# Sensors.net
KiCad netlist of a schematic drawn in Altium Designer
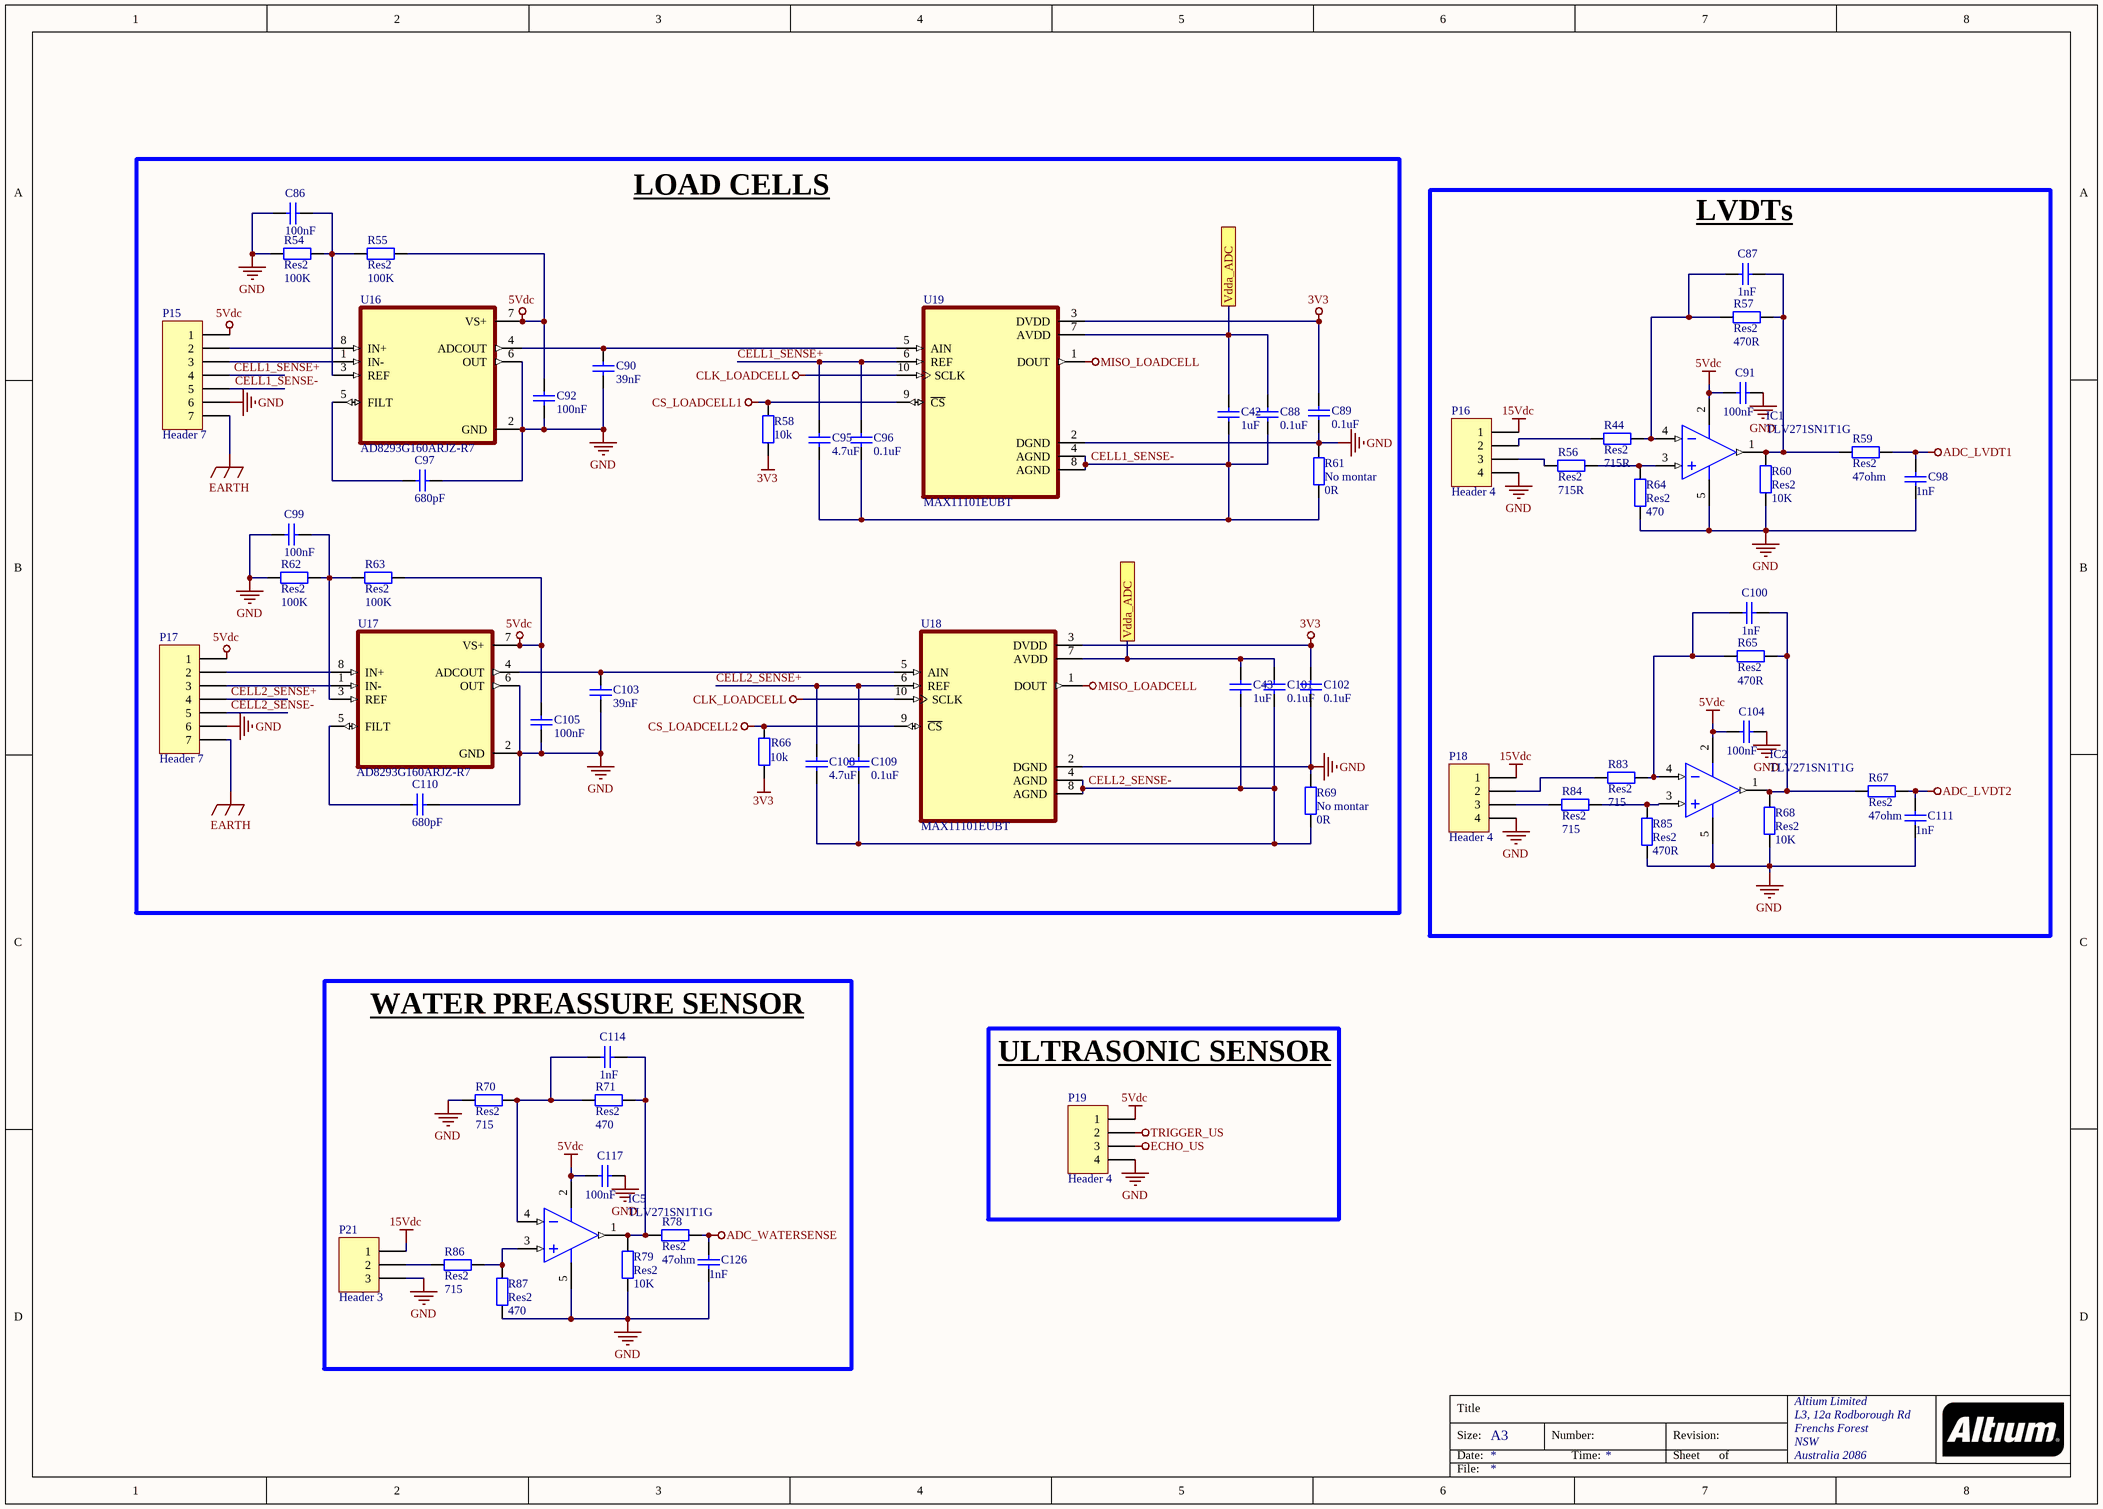
[diagram p0: Sensors.SchDoc]

(export (version "E")
  (design (tool "Eeschema 10.0.6"))
  (components
    (comp (ref "C42")
      (value "1uF")
      (footprint "Miscellaneous Devices:0603 - duplicate")
      (description "Capacitor")
      (fields (field (name "Comment") "Cap") (field (name "PUBLISHER") "Altium Limited"))
      (libsource (lib "Miscellaneous Devices") (part "Cap"))
    )
    (comp (ref "C43")
      (value "1uF")
      (footprint "Miscellaneous Devices:0603 - duplicate")
      (description "Capacitor")
      (fields (field (name "Comment") "Cap") (field (name "PUBLISHER") "Altium Limited"))
      (libsource (lib "Miscellaneous Devices") (part "Cap"))
    )
    (comp (ref "C86")
      (value "100nF")
      (footprint "Miscellaneous Devices:0603 - duplicate")
      (description "Capacitor")
      (fields (field (name "Comment") "Cap") (field (name "PUBLISHER") "Altium Limited"))
      (libsource (lib "Miscellaneous Devices") (part "Cap"))
    )
    (comp (ref "C87")
      (value "1nF")
      (footprint "Miscellaneous Devices:0603 - duplicate")
      (description "Capacitor")
      (fields (field (name "Comment") "Cap") (field (name "PUBLISHER") "Altium Limited"))
      (libsource (lib "Miscellaneous Devices") (part "Cap"))
    )
    (comp (ref "C88")
      (value "0.1uF")
      (footprint "Miscellaneous Devices:0603 - duplicate")
      (description "Capacitor")
      (fields (field (name "Comment") "Cap") (field (name "PUBLISHER") "Altium Limited"))
      (libsource (lib "Miscellaneous Devices") (part "Cap"))
    )
    (comp (ref "C89")
      (value "0.1uF")
      (footprint "Miscellaneous Devices:0603 - duplicate")
      (description "Capacitor")
      (fields (field (name "Comment") "Cap") (field (name "PUBLISHER") "Altium Limited"))
      (libsource (lib "Miscellaneous Devices") (part "Cap"))
    )
    (comp (ref "C90")
      (value "39nF")
      (footprint "Miscellaneous Devices:0603 - duplicate")
      (description "Capacitor")
      (fields (field (name "Comment") "Cap") (field (name "PUBLISHER") "Altium Limited"))
      (libsource (lib "Miscellaneous Devices") (part "Cap"))
    )
    (comp (ref "C91")
      (value "100nF")
      (footprint "Miscellaneous Devices:0603 - duplicate")
      (description "Capacitor")
      (fields (field (name "Comment") "Cap") (field (name "PUBLISHER") "Altium Limited"))
      (libsource (lib "Miscellaneous Devices") (part "Cap"))
    )
    (comp (ref "C92")
      (value "100nF")
      (footprint "Miscellaneous Devices:0603 - duplicate")
      (description "Capacitor")
      (fields (field (name "Comment") "Cap") (field (name "PUBLISHER") "Altium Limited"))
      (libsource (lib "Miscellaneous Devices") (part "Cap"))
    )
    (comp (ref "C95")
      (value "4.7uF")
      (footprint "Miscellaneous Devices:0603 - duplicate")
      (description "Capacitor")
      (fields (field (name "Comment") "Cap") (field (name "PUBLISHER") "Altium Limited"))
      (libsource (lib "Miscellaneous Devices") (part "Cap"))
    )
    (comp (ref "C96")
      (value "0.1uF")
      (footprint "Miscellaneous Devices:0603 - duplicate")
      (description "Capacitor")
      (fields (field (name "Comment") "Cap") (field (name "PUBLISHER") "Altium Limited"))
      (libsource (lib "Miscellaneous Devices") (part "Cap"))
    )
    (comp (ref "C97")
      (value "680pF")
      (footprint "Miscellaneous Devices:0603 - duplicate")
      (description "Capacitor")
      (fields (field (name "Comment") "Cap") (field (name "PUBLISHER") "Altium Limited"))
      (libsource (lib "Miscellaneous Devices") (part "Cap"))
    )
    (comp (ref "C98")
      (value "1nF")
      (footprint "Miscellaneous Devices:0603 - duplicate")
      (description "Capacitor")
      (fields (field (name "Comment") "Cap") (field (name "PUBLISHER") "Altium Limited"))
      (libsource (lib "Miscellaneous Devices") (part "Cap"))
    )
    (comp (ref "C99")
      (value "100nF")
      (footprint "Miscellaneous Devices:0603 - duplicate")
      (description "Capacitor")
      (fields (field (name "Comment") "Cap") (field (name "PUBLISHER") "Altium Limited"))
      (libsource (lib "Miscellaneous Devices") (part "Cap"))
    )
    (comp (ref "C100")
      (value "1nF")
      (footprint "Miscellaneous Devices:0603 - duplicate")
      (description "Capacitor")
      (fields (field (name "Comment") "Cap") (field (name "PUBLISHER") "Altium Limited"))
      (libsource (lib "Miscellaneous Devices") (part "Cap"))
    )
    (comp (ref "C101")
      (value "0.1uF")
      (footprint "Miscellaneous Devices:0603 - duplicate")
      (description "Capacitor")
      (fields (field (name "Comment") "Cap") (field (name "PUBLISHER") "Altium Limited"))
      (libsource (lib "Miscellaneous Devices") (part "Cap"))
    )
    (comp (ref "C102")
      (value "0.1uF")
      (footprint "Miscellaneous Devices:0603 - duplicate")
      (description "Capacitor")
      (fields (field (name "Comment") "Cap") (field (name "PUBLISHER") "Altium Limited"))
      (libsource (lib "Miscellaneous Devices") (part "Cap"))
    )
    (comp (ref "C103")
      (value "39nF")
      (footprint "Miscellaneous Devices:0603 - duplicate")
      (description "Capacitor")
      (fields (field (name "Comment") "Cap") (field (name "PUBLISHER") "Altium Limited"))
      (libsource (lib "Miscellaneous Devices") (part "Cap"))
    )
    (comp (ref "C104")
      (value "100nF")
      (footprint "Miscellaneous Devices:0603 - duplicate")
      (description "Capacitor")
      (fields (field (name "Comment") "Cap") (field (name "PUBLISHER") "Altium Limited"))
      (libsource (lib "Miscellaneous Devices") (part "Cap"))
    )
    (comp (ref "C105")
      (value "100nF")
      (footprint "Miscellaneous Devices:0603 - duplicate")
      (description "Capacitor")
      (fields (field (name "Comment") "Cap") (field (name "PUBLISHER") "Altium Limited"))
      (libsource (lib "Miscellaneous Devices") (part "Cap"))
    )
    (comp (ref "C108")
      (value "4.7uF")
      (footprint "Miscellaneous Devices:0603 - duplicate")
      (description "Capacitor")
      (fields (field (name "Comment") "Cap") (field (name "PUBLISHER") "Altium Limited"))
      (libsource (lib "Miscellaneous Devices") (part "Cap"))
    )
    (comp (ref "C109")
      (value "0.1uF")
      (footprint "Miscellaneous Devices:0603 - duplicate")
      (description "Capacitor")
      (fields (field (name "Comment") "Cap") (field (name "PUBLISHER") "Altium Limited"))
      (libsource (lib "Miscellaneous Devices") (part "Cap"))
    )
    (comp (ref "C110")
      (value "680pF")
      (footprint "Miscellaneous Devices:0603 - duplicate")
      (description "Capacitor")
      (fields (field (name "Comment") "Cap") (field (name "PUBLISHER") "Altium Limited"))
      (libsource (lib "Miscellaneous Devices") (part "Cap"))
    )
    (comp (ref "C111")
      (value "1nF")
      (footprint "Miscellaneous Devices:0603 - duplicate")
      (description "Capacitor")
      (fields (field (name "Comment") "Cap") (field (name "PUBLISHER") "Altium Limited"))
      (libsource (lib "Miscellaneous Devices") (part "Cap"))
    )
    (comp (ref "C114")
      (value "1nF")
      (footprint "Miscellaneous Devices:0603 - duplicate")
      (description "Capacitor")
      (fields (field (name "Comment") "Cap") (field (name "PUBLISHER") "Altium Limited"))
      (libsource (lib "Miscellaneous Devices") (part "Cap"))
    )
    (comp (ref "C117")
      (value "100nF")
      (footprint "Miscellaneous Devices:0603 - duplicate")
      (description "Capacitor")
      (fields (field (name "Comment") "Cap") (field (name "PUBLISHER") "Altium Limited"))
      (libsource (lib "Miscellaneous Devices") (part "Cap"))
    )
    (comp (ref "C126")
      (value "1nF")
      (footprint "Miscellaneous Devices:0603 - duplicate")
      (description "Capacitor")
      (fields (field (name "Comment") "Cap") (field (name "PUBLISHER") "Altium Limited"))
      (libsource (lib "Miscellaneous Devices") (part "Cap"))
    )
    (comp (ref "IC1")
      (value "TLV271SN1T1G")
      (footprint "Miscellaneous Devices:SOT23-5_N")
      (description "Operational Amplifier")
      (fields (field (name "PUBLISHER") "Altium Limited"))
      (libsource (lib "Miscellaneous Devices") (part "TLV271SN1T1G"))
    )
    (comp (ref "IC2")
      (value "TLV271SN1T1G")
      (footprint "Miscellaneous Devices:SOT23-5_N")
      (description "Operational Amplifier")
      (fields (field (name "PUBLISHER") "Altium Limited"))
      (libsource (lib "Miscellaneous Devices") (part "TLV271SN1T1G"))
    )
    (comp (ref "IC5")
      (value "TLV271SN1T1G")
      (footprint "Miscellaneous Devices:SOT23-5_N")
      (description "Operational Amplifier")
      (fields (field (name "PUBLISHER") "Altium Limited"))
      (libsource (lib "Miscellaneous Devices") (part "TLV271SN1T1G"))
    )
    (comp (ref "P15")
      (value "Header 7")
      (footprint "Miscellaneous Connectors:regleta_7")
      (description "Header, 7-Pin")
      (fields (field (name "PUBLISHER") "Altium Limited"))
      (libsource (lib "Miscellaneous Connectors") (part "Header 7"))
    )
    (comp (ref "P16")
      (value "Header 4")
      (footprint "Miscellaneous Connectors:regleta_4")
      (description "Header, 4-Pin")
      (fields (field (name "PUBLISHER") "Altium Limited"))
      (libsource (lib "Miscellaneous Connectors") (part "Header 4"))
    )
    (comp (ref "P17")
      (value "Header 7")
      (footprint "Miscellaneous Connectors:regleta_7")
      (description "Header, 7-Pin")
      (fields (field (name "PUBLISHER") "Altium Limited"))
      (libsource (lib "Miscellaneous Connectors") (part "Header 7"))
    )
    (comp (ref "P18")
      (value "Header 4")
      (footprint "Miscellaneous Connectors:regleta_4")
      (description "Header, 4-Pin")
      (fields (field (name "PUBLISHER") "Altium Limited"))
      (libsource (lib "Miscellaneous Connectors") (part "Header 4"))
    )
    (comp (ref "P19")
      (value "Header 4")
      (footprint "Miscellaneous Connectors:regleta_4")
      (description "Header, 4-Pin")
      (fields (field (name "PUBLISHER") "Altium Limited"))
      (libsource (lib "Miscellaneous Connectors") (part "Header 4"))
    )
    (comp (ref "P21")
      (value "Header 3")
      (footprint "Miscellaneous Connectors:regleta_3")
      (description "Header, 3-Pin")
      (fields (field (name "PUBLISHER") "Altium Limited"))
      (libsource (lib "Miscellaneous Connectors") (part "Header 3"))
    )
    (comp (ref "R44")
      (value "Res2")
      (footprint "Miscellaneous Devices:0603 - duplicate")
      (description "Resistor")
      (fields (field (name "ALTIUM_VALUE") "715R") (field (name "PUBLISHER") "Altium Limited"))
      (libsource (lib "Miscellaneous Devices") (part "Res2"))
    )
    (comp (ref "R54")
      (value "Res2")
      (footprint "Miscellaneous Devices:0603 - duplicate")
      (description "Resistor")
      (fields (field (name "ALTIUM_VALUE") "100K") (field (name "PUBLISHER") "Altium Limited"))
      (libsource (lib "Miscellaneous Devices") (part "Res2"))
    )
    (comp (ref "R55")
      (value "Res2")
      (footprint "Miscellaneous Devices:0603 - duplicate")
      (description "Resistor")
      (fields (field (name "ALTIUM_VALUE") "100K") (field (name "PUBLISHER") "Altium Limited"))
      (libsource (lib "Miscellaneous Devices") (part "Res2"))
    )
    (comp (ref "R56")
      (value "Res2")
      (footprint "Miscellaneous Devices:0603 - duplicate")
      (description "Resistor")
      (fields (field (name "ALTIUM_VALUE") "715R") (field (name "PUBLISHER") "Altium Limited"))
      (libsource (lib "Miscellaneous Devices") (part "Res2"))
    )
    (comp (ref "R57")
      (value "Res2")
      (footprint "Miscellaneous Devices:0603 - duplicate")
      (description "Resistor")
      (fields (field (name "ALTIUM_VALUE") "470R") (field (name "PUBLISHER") "Altium Limited"))
      (libsource (lib "Miscellaneous Devices") (part "Res2"))
    )
    (comp (ref "R58")
      (value "10k")
      (footprint "Miscellaneous Devices:0603 - duplicate")
      (description "Resistor")
      (fields (field (name "PUBLISHER") "Altium Limited"))
      (libsource (lib "") (part "Res2_2"))
    )
    (comp (ref "R59")
      (value "Res2")
      (footprint "Miscellaneous Devices:0603 - duplicate")
      (description "Resistor")
      (fields (field (name "ALTIUM_VALUE") "47ohm") (field (name "PUBLISHER") "Altium Limited"))
      (libsource (lib "Miscellaneous Devices") (part "Res2"))
    )
    (comp (ref "R60")
      (value "Res2")
      (footprint "Miscellaneous Devices:0603 - duplicate")
      (description "Resistor")
      (fields (field (name "ALTIUM_VALUE") "10K") (field (name "PUBLISHER") "Altium Limited"))
      (libsource (lib "") (part "Res2_1"))
    )
    (comp (ref "R61")
      (value "No montar")
      (footprint "Miscellaneous Devices:0603 - duplicate")
      (description "Resistor")
      (fields (field (name "ALTIUM_VALUE") "0R") (field (name "PUBLISHER") "Altium Limited"))
      (libsource (lib "") (part "Res2_1"))
    )
    (comp (ref "R62")
      (value "Res2")
      (footprint "Miscellaneous Devices:0603 - duplicate")
      (description "Resistor")
      (fields (field (name "ALTIUM_VALUE") "100K") (field (name "PUBLISHER") "Altium Limited"))
      (libsource (lib "Miscellaneous Devices") (part "Res2"))
    )
    (comp (ref "R63")
      (value "Res2")
      (footprint "Miscellaneous Devices:0603 - duplicate")
      (description "Resistor")
      (fields (field (name "ALTIUM_VALUE") "100K") (field (name "PUBLISHER") "Altium Limited"))
      (libsource (lib "Miscellaneous Devices") (part "Res2"))
    )
    (comp (ref "R64")
      (value "Res2")
      (footprint "Miscellaneous Devices:0603 - duplicate")
      (description "Resistor")
      (fields (field (name "ALTIUM_VALUE") "470") (field (name "PUBLISHER") "Altium Limited"))
      (libsource (lib "") (part "Res2_2"))
    )
    (comp (ref "R65")
      (value "Res2")
      (footprint "Miscellaneous Devices:0603 - duplicate")
      (description "Resistor")
      (fields (field (name "ALTIUM_VALUE") "470R") (field (name "PUBLISHER") "Altium Limited"))
      (libsource (lib "Miscellaneous Devices") (part "Res2"))
    )
    (comp (ref "R66")
      (value "10k")
      (footprint "Miscellaneous Devices:0603 - duplicate")
      (description "Resistor")
      (fields (field (name "PUBLISHER") "Altium Limited"))
      (libsource (lib "") (part "Res2_2"))
    )
    (comp (ref "R67")
      (value "Res2")
      (footprint "Miscellaneous Devices:0603 - duplicate")
      (description "Resistor")
      (fields (field (name "ALTIUM_VALUE") "47ohm") (field (name "PUBLISHER") "Altium Limited"))
      (libsource (lib "Miscellaneous Devices") (part "Res2"))
    )
    (comp (ref "R68")
      (value "Res2")
      (footprint "Miscellaneous Devices:0603 - duplicate")
      (description "Resistor")
      (fields (field (name "ALTIUM_VALUE") "10K") (field (name "PUBLISHER") "Altium Limited"))
      (libsource (lib "") (part "Res2_1"))
    )
    (comp (ref "R69")
      (value "No montar")
      (footprint "Miscellaneous Devices:0603 - duplicate")
      (description "Resistor")
      (fields (field (name "ALTIUM_VALUE") "0R") (field (name "PUBLISHER") "Altium Limited"))
      (libsource (lib "") (part "Res2_1"))
    )
    (comp (ref "R70")
      (value "Res2")
      (footprint "Miscellaneous Devices:0603 - duplicate")
      (description "Resistor")
      (fields (field (name "ALTIUM_VALUE") "715") (field (name "PUBLISHER") "Altium Limited"))
      (libsource (lib "Miscellaneous Devices") (part "Res2"))
    )
    (comp (ref "R71")
      (value "Res2")
      (footprint "Miscellaneous Devices:0603 - duplicate")
      (description "Resistor")
      (fields (field (name "ALTIUM_VALUE") "470") (field (name "PUBLISHER") "Altium Limited"))
      (libsource (lib "Miscellaneous Devices") (part "Res2"))
    )
    (comp (ref "R78")
      (value "Res2")
      (footprint "Miscellaneous Devices:0603 - duplicate")
      (description "Resistor")
      (fields (field (name "ALTIUM_VALUE") "47ohm") (field (name "PUBLISHER") "Altium Limited"))
      (libsource (lib "Miscellaneous Devices") (part "Res2"))
    )
    (comp (ref "R79")
      (value "Res2")
      (footprint "Miscellaneous Devices:0603 - duplicate")
      (description "Resistor")
      (fields (field (name "ALTIUM_VALUE") "10K") (field (name "PUBLISHER") "Altium Limited"))
      (libsource (lib "") (part "Res2_1"))
    )
    (comp (ref "R83")
      (value "Res2")
      (footprint "Miscellaneous Devices:0603 - duplicate")
      (description "Resistor")
      (fields (field (name "ALTIUM_VALUE") "715") (field (name "PUBLISHER") "Altium Limited"))
      (libsource (lib "Miscellaneous Devices") (part "Res2"))
    )
    (comp (ref "R84")
      (value "Res2")
      (footprint "Miscellaneous Devices:0603 - duplicate")
      (description "Resistor")
      (fields (field (name "ALTIUM_VALUE") "715") (field (name "PUBLISHER") "Altium Limited"))
      (libsource (lib "Miscellaneous Devices") (part "Res2"))
    )
    (comp (ref "R85")
      (value "Res2")
      (footprint "Miscellaneous Devices:0603 - duplicate")
      (description "Resistor")
      (fields (field (name "ALTIUM_VALUE") "470R") (field (name "PUBLISHER") "Altium Limited"))
      (libsource (lib "") (part "Res2_2"))
    )
    (comp (ref "R86")
      (value "Res2")
      (footprint "Miscellaneous Devices:0603 - duplicate")
      (description "Resistor")
      (fields (field (name "ALTIUM_VALUE") "715") (field (name "PUBLISHER") "Altium Limited"))
      (libsource (lib "Miscellaneous Devices") (part "Res2"))
    )
    (comp (ref "R87")
      (value "Res2")
      (footprint "Miscellaneous Devices:0603 - duplicate")
      (description "Resistor")
      (fields (field (name "ALTIUM_VALUE") "470") (field (name "PUBLISHER") "Altium Limited"))
      (libsource (lib "") (part "Res2_2"))
    )
    (comp (ref "U16")
      (value "AD8293G160ARJZ-R7")
      (footprint "Miscellaneous Devices:SOT65P280X145-8N")
      (description "Instrumentation Amplifier 1 Circuit Rail-to-Rail SOT-23-8")
      (fields (field (name "MF") "Analog Devices"))
      (libsource (lib "Miscellaneous Devices") (part "AD8293G160ARJZ-R7"))
    )
    (comp (ref "U17")
      (value "AD8293G160ARJZ-R7")
      (footprint "Miscellaneous Devices:SOT65P280X145-8N")
      (description "Instrumentation Amplifier 1 Circuit Rail-to-Rail SOT-23-8")
      (fields (field (name "MF") "Analog Devices"))
      (libsource (lib "Miscellaneous Devices") (part "AD8293G160ARJZ-R7"))
    )
    (comp (ref "U18")
      (value "MAX11101EUBT")
      (footprint "Miscellaneous Devices:SOP50P490X110-10N")
      (description "Data acquisition IC - AD converter _ADC_ Maxim Integrated MAX11101EUB+T External uMAX 10")
      (fields (field (name "MP") "MAX11101EUB+T") (field (name "MF") "Maxim Integrated"))
      (libsource (lib "Miscellaneous Devices") (part "MAX11101EUBT"))
    )
    (comp (ref "U19")
      (value "MAX11101EUBT")
      (footprint "Miscellaneous Devices:SOP50P490X110-10N")
      (description "Data acquisition IC - AD converter _ADC_ Maxim Integrated MAX11101EUB+T External uMAX 10")
      (fields (field (name "MP") "MAX11101EUB+T") (field (name "MF") "Maxim Integrated"))
      (libsource (lib "Miscellaneous Devices") (part "MAX11101EUBT"))
    )
  )
  (nets
    (net (code "1") (name "/CELL1_SENSE+") (class "Default")
      (node (ref "C95") (pin "2") (pinfunction "2_2") (pintype "passive"))
      (node (ref "C96") (pin "2") (pinfunction "2_2") (pintype "passive"))
      (node (ref "P15") (pin "4") (pinfunction "4_4") (pintype "passive"))
      (node (ref "U19") (pin "6") (pinfunction "REF_6") (pintype "input"))
    )
    (net (code "2") (name "/CELL1_SENSE-") (class "Default")
      (node (ref "C42") (pin "1") (pinfunction "1_1") (pintype "passive"))
      (node (ref "C88") (pin "1") (pinfunction "1_1") (pintype "passive"))
      (node (ref "C95") (pin "1") (pinfunction "1_1") (pintype "passive"))
      (node (ref "C96") (pin "1") (pinfunction "1_1") (pintype "passive"))
      (node (ref "P15") (pin "5") (pinfunction "5_5") (pintype "passive"))
      (node (ref "R61") (pin "1") (pinfunction "1_1") (pintype "passive"))
      (node (ref "U19") (pin "4") (pinfunction "AGND_4") (pintype "power_in"))
      (node (ref "U19") (pin "8") (pinfunction "AGND_8") (pintype "power_in"))
    )
    (net (code "3") (name "/CELL2_SENSE+") (class "Default")
      (node (ref "C108") (pin "2") (pinfunction "2_2") (pintype "passive"))
      (node (ref "C109") (pin "2") (pinfunction "2_2") (pintype "passive"))
      (node (ref "P17") (pin "4") (pinfunction "4_4") (pintype "passive"))
      (node (ref "U18") (pin "6") (pinfunction "REF_6") (pintype "input"))
    )
    (net (code "4") (name "/CELL2_SENSE-") (class "Default")
      (node (ref "C101") (pin "1") (pinfunction "1_1") (pintype "passive"))
      (node (ref "C108") (pin "1") (pinfunction "1_1") (pintype "passive"))
      (node (ref "C109") (pin "1") (pinfunction "1_1") (pintype "passive"))
      (node (ref "C43") (pin "1") (pinfunction "1_1") (pintype "passive"))
      (node (ref "P17") (pin "5") (pinfunction "5_5") (pintype "passive"))
      (node (ref "R69") (pin "1") (pinfunction "1_1") (pintype "passive"))
      (node (ref "U18") (pin "4") (pinfunction "AGND_4") (pintype "power_in"))
      (node (ref "U18") (pin "8") (pinfunction "AGND_8") (pintype "power_in"))
    )
    (net (code "5") (name "/Vdda_ADC") (class "Default")
      (node (ref "C101") (pin "2") (pinfunction "2_2") (pintype "passive"))
      (node (ref "C42") (pin "2") (pinfunction "2_2") (pintype "passive"))
      (node (ref "C43") (pin "2") (pinfunction "2_2") (pintype "passive"))
      (node (ref "C88") (pin "2") (pinfunction "2_2") (pintype "passive"))
      (node (ref "U18") (pin "7") (pinfunction "AVDD_7") (pintype "power_in"))
      (node (ref "U19") (pin "7") (pinfunction "AVDD_7") (pintype "power_in"))
    )
    (net (code "6") (name "3V3") (class "Default")
      (node (ref "C102") (pin "2") (pinfunction "2_2") (pintype "passive"))
      (node (ref "C89") (pin "2") (pinfunction "2_2") (pintype "passive"))
      (node (ref "R58") (pin "2") (pinfunction "2_2") (pintype "passive"))
      (node (ref "R66") (pin "2") (pinfunction "2_2") (pintype "passive"))
      (node (ref "U18") (pin "3") (pinfunction "DVDD_3") (pintype "power_in"))
      (node (ref "U19") (pin "3") (pinfunction "DVDD_3") (pintype "power_in"))
    )
    (net (code "7") (name "5Vdc") (class "Default")
      (node (ref "C104") (pin "1") (pinfunction "1_1") (pintype "passive"))
      (node (ref "C105") (pin "2") (pinfunction "2_2") (pintype "passive"))
      (node (ref "C117") (pin "1") (pinfunction "1_1") (pintype "passive"))
      (node (ref "C91") (pin "1") (pinfunction "1_1") (pintype "passive"))
      (node (ref "C92") (pin "2") (pinfunction "2_2") (pintype "passive"))
      (node (ref "IC1") (pin "2") (pinfunction "V+_2") (pintype "power_in"))
      (node (ref "IC2") (pin "2") (pinfunction "V+_2") (pintype "power_in"))
      (node (ref "IC5") (pin "2") (pinfunction "V+_2") (pintype "power_in"))
      (node (ref "P15") (pin "1") (pinfunction "1_1") (pintype "passive"))
      (node (ref "P17") (pin "1") (pinfunction "1_1") (pintype "passive"))
      (node (ref "P19") (pin "1") (pinfunction "1_1") (pintype "passive"))
      (node (ref "R55") (pin "1") (pinfunction "1_1") (pintype "passive"))
      (node (ref "R63") (pin "1") (pinfunction "1_1") (pintype "passive"))
      (node (ref "U16") (pin "7") (pinfunction "VS+_7") (pintype "power_in"))
      (node (ref "U17") (pin "7") (pinfunction "VS+_7") (pintype "power_in"))
    )
    (net (code "8") (name "15Vdc") (class "Default")
      (node (ref "P16") (pin "1") (pinfunction "1_1") (pintype "passive"))
      (node (ref "P18") (pin "1") (pinfunction "1_1") (pintype "passive"))
      (node (ref "P21") (pin "1") (pinfunction "1_1") (pintype "passive"))
    )
    (net (code "9") (name "ADC_LVDT1") (class "Default")
      (node (ref "C98") (pin "2") (pinfunction "2_2") (pintype "passive"))
      (node (ref "R59") (pin "1") (pinfunction "1_1") (pintype "passive"))
    )
    (net (code "10") (name "ADC_LVDT2") (class "Default")
      (node (ref "C111") (pin "2") (pinfunction "2_2") (pintype "passive"))
      (node (ref "R67") (pin "1") (pinfunction "1_1") (pintype "passive"))
    )
    (net (code "11") (name "ADC_WATERSENSE") (class "Default")
      (node (ref "C126") (pin "2") (pinfunction "2_2") (pintype "passive"))
      (node (ref "R78") (pin "1") (pinfunction "1_1") (pintype "passive"))
    )
    (net (code "12") (name "CLK_LOADCELL") (class "Default")
      (node (ref "U18") (pin "10") (pinfunction "SCLK_10") (pintype "input"))
      (node (ref "U19") (pin "10") (pinfunction "SCLK_10") (pintype "input"))
    )
    (net (code "13") (name "CS_LOADCELL1") (class "Default")
      (node (ref "R58") (pin "1") (pinfunction "1_1") (pintype "passive"))
      (node (ref "U19") (pin "9") (pinfunction "~{CS}_9") (pintype "bidirectional"))
    )
    (net (code "14") (name "CS_LOADCELL2") (class "Default")
      (node (ref "R66") (pin "1") (pinfunction "1_1") (pintype "passive"))
      (node (ref "U18") (pin "9") (pinfunction "~{CS}_9") (pintype "bidirectional"))
    )
    (net (code "15") (name "EARTH") (class "Default")
      (node (ref "P15") (pin "7") (pinfunction "7_7") (pintype "passive"))
      (node (ref "P17") (pin "7") (pinfunction "7_7") (pintype "passive"))
    )
    (net (code "16") (name "ECHO_US") (class "Default")
      (node (ref "P19") (pin "3") (pinfunction "3_3") (pintype "passive"))
    )
    (net (code "17") (name "GND") (class "Default")
      (node (ref "C102") (pin "1") (pinfunction "1_1") (pintype "passive"))
      (node (ref "C103") (pin "1") (pinfunction "1_1") (pintype "passive"))
      (node (ref "C104") (pin "2") (pinfunction "2_2") (pintype "passive"))
      (node (ref "C105") (pin "1") (pinfunction "1_1") (pintype "passive"))
      (node (ref "C110") (pin "1") (pinfunction "1_1") (pintype "passive"))
      (node (ref "C111") (pin "1") (pinfunction "1_1") (pintype "passive"))
      (node (ref "C117") (pin "2") (pinfunction "2_2") (pintype "passive"))
      (node (ref "C126") (pin "1") (pinfunction "1_1") (pintype "passive"))
      (node (ref "C86") (pin "2") (pinfunction "2_2") (pintype "passive"))
      (node (ref "C89") (pin "1") (pinfunction "1_1") (pintype "passive"))
      (node (ref "C90") (pin "1") (pinfunction "1_1") (pintype "passive"))
      (node (ref "C91") (pin "2") (pinfunction "2_2") (pintype "passive"))
      (node (ref "C92") (pin "1") (pinfunction "1_1") (pintype "passive"))
      (node (ref "C97") (pin "1") (pinfunction "1_1") (pintype "passive"))
      (node (ref "C98") (pin "1") (pinfunction "1_1") (pintype "passive"))
      (node (ref "C99") (pin "2") (pinfunction "2_2") (pintype "passive"))
      (node (ref "IC1") (pin "5") (pinfunction "V-_5") (pintype "power_in"))
      (node (ref "IC2") (pin "5") (pinfunction "V-_5") (pintype "power_in"))
      (node (ref "IC5") (pin "5") (pinfunction "V-_5") (pintype "power_in"))
      (node (ref "P15") (pin "6") (pinfunction "6_6") (pintype "passive"))
      (node (ref "P16") (pin "4") (pinfunction "4_4") (pintype "passive"))
      (node (ref "P17") (pin "6") (pinfunction "6_6") (pintype "passive"))
      (node (ref "P18") (pin "4") (pinfunction "4_4") (pintype "passive"))
      (node (ref "P19") (pin "4") (pinfunction "4_4") (pintype "passive"))
      (node (ref "P21") (pin "3") (pinfunction "3_3") (pintype "passive"))
      (node (ref "R54") (pin "2") (pinfunction "2_2") (pintype "passive"))
      (node (ref "R60") (pin "1") (pinfunction "1_1") (pintype "passive"))
      (node (ref "R61") (pin "2") (pinfunction "2_2") (pintype "passive"))
      (node (ref "R62") (pin "2") (pinfunction "2_2") (pintype "passive"))
      (node (ref "R64") (pin "2") (pinfunction "2_2") (pintype "passive"))
      (node (ref "R68") (pin "1") (pinfunction "1_1") (pintype "passive"))
      (node (ref "R69") (pin "2") (pinfunction "2_2") (pintype "passive"))
      (node (ref "R70") (pin "2") (pinfunction "2_2") (pintype "passive"))
      (node (ref "R79") (pin "1") (pinfunction "1_1") (pintype "passive"))
      (node (ref "R85") (pin "2") (pinfunction "2_2") (pintype "passive"))
      (node (ref "R87") (pin "2") (pinfunction "2_2") (pintype "passive"))
      (node (ref "U16") (pin "2") (pinfunction "GND_2") (pintype "power_in"))
      (node (ref "U16") (pin "6") (pinfunction "OUT_6") (pintype "output"))
      (node (ref "U17") (pin "2") (pinfunction "GND_2") (pintype "power_in"))
      (node (ref "U17") (pin "6") (pinfunction "OUT_6") (pintype "output"))
      (node (ref "U18") (pin "2") (pinfunction "DGND_2") (pintype "power_in"))
      (node (ref "U19") (pin "2") (pinfunction "DGND_2") (pintype "power_in"))
    )
    (net (code "18") (name "MISO_LOADCELL") (class "Default")
      (node (ref "U18") (pin "1") (pinfunction "DOUT_1") (pintype "output"))
      (node (ref "U19") (pin "1") (pinfunction "DOUT_1") (pintype "output"))
    )
    (net (code "19") (name "Net-(IC1-IN+)") (class "Default")
      (node (ref "IC1") (pin "3") (pinfunction "IN+_3") (pintype "input"))
      (node (ref "R56") (pin "1") (pinfunction "1_1") (pintype "passive"))
      (node (ref "R64") (pin "1") (pinfunction "1_1") (pintype "passive"))
    )
    (net (code "20") (name "Net-(IC1-IN-)") (class "Default")
      (node (ref "C87") (pin "2") (pinfunction "2_2") (pintype "passive"))
      (node (ref "IC1") (pin "4") (pinfunction "IN-_4") (pintype "input"))
      (node (ref "R44") (pin "1") (pinfunction "1_1") (pintype "passive"))
      (node (ref "R57") (pin "2") (pinfunction "2_2") (pintype "passive"))
    )
    (net (code "21") (name "Net-(IC1-OUT)") (class "Default")
      (node (ref "C87") (pin "1") (pinfunction "1_1") (pintype "passive"))
      (node (ref "IC1") (pin "1") (pinfunction "OUT_1") (pintype "output"))
      (node (ref "R57") (pin "1") (pinfunction "1_1") (pintype "passive"))
      (node (ref "R59") (pin "2") (pinfunction "2_2") (pintype "passive"))
      (node (ref "R60") (pin "2") (pinfunction "2_2") (pintype "passive"))
    )
    (net (code "22") (name "Net-(IC2-IN+)") (class "Default")
      (node (ref "IC2") (pin "3") (pinfunction "IN+_3") (pintype "input"))
      (node (ref "R84") (pin "1") (pinfunction "1_1") (pintype "passive"))
      (node (ref "R85") (pin "1") (pinfunction "1_1") (pintype "passive"))
    )
    (net (code "23") (name "Net-(IC2-IN-)") (class "Default")
      (node (ref "C100") (pin "2") (pinfunction "2_2") (pintype "passive"))
      (node (ref "IC2") (pin "4") (pinfunction "IN-_4") (pintype "input"))
      (node (ref "R65") (pin "2") (pinfunction "2_2") (pintype "passive"))
      (node (ref "R83") (pin "1") (pinfunction "1_1") (pintype "passive"))
    )
    (net (code "24") (name "Net-(IC2-OUT)") (class "Default")
      (node (ref "C100") (pin "1") (pinfunction "1_1") (pintype "passive"))
      (node (ref "IC2") (pin "1") (pinfunction "OUT_1") (pintype "output"))
      (node (ref "R65") (pin "1") (pinfunction "1_1") (pintype "passive"))
      (node (ref "R67") (pin "2") (pinfunction "2_2") (pintype "passive"))
      (node (ref "R68") (pin "2") (pinfunction "2_2") (pintype "passive"))
    )
    (net (code "25") (name "Net-(IC5-IN+)") (class "Default")
      (node (ref "IC5") (pin "3") (pinfunction "IN+_3") (pintype "input"))
      (node (ref "R86") (pin "1") (pinfunction "1_1") (pintype "passive"))
      (node (ref "R87") (pin "1") (pinfunction "1_1") (pintype "passive"))
    )
    (net (code "26") (name "Net-(IC5-IN-)") (class "Default")
      (node (ref "C114") (pin "2") (pinfunction "2_2") (pintype "passive"))
      (node (ref "IC5") (pin "4") (pinfunction "IN-_4") (pintype "input"))
      (node (ref "R70") (pin "1") (pinfunction "1_1") (pintype "passive"))
      (node (ref "R71") (pin "2") (pinfunction "2_2") (pintype "passive"))
    )
    (net (code "27") (name "Net-(IC5-OUT)") (class "Default")
      (node (ref "C114") (pin "1") (pinfunction "1_1") (pintype "passive"))
      (node (ref "IC5") (pin "1") (pinfunction "OUT_1") (pintype "output"))
      (node (ref "R71") (pin "1") (pinfunction "1_1") (pintype "passive"))
      (node (ref "R78") (pin "2") (pinfunction "2_2") (pintype "passive"))
      (node (ref "R79") (pin "2") (pinfunction "2_2") (pintype "passive"))
    )
    (net (code "28") (name "Net-(P16-Pad2)") (class "Default")
      (node (ref "P16") (pin "2") (pinfunction "2_2") (pintype "passive"))
      (node (ref "R44") (pin "2") (pinfunction "2_2") (pintype "passive"))
    )
    (net (code "29") (name "Net-(P16-Pad3)") (class "Default")
      (node (ref "P16") (pin "3") (pinfunction "3_3") (pintype "passive"))
      (node (ref "R56") (pin "2") (pinfunction "2_2") (pintype "passive"))
    )
    (net (code "30") (name "Net-(P18-Pad2)") (class "Default")
      (node (ref "P18") (pin "2") (pinfunction "2_2") (pintype "passive"))
      (node (ref "R83") (pin "2") (pinfunction "2_2") (pintype "passive"))
    )
    (net (code "31") (name "Net-(P18-Pad3)") (class "Default")
      (node (ref "P18") (pin "3") (pinfunction "3_3") (pintype "passive"))
      (node (ref "R84") (pin "2") (pinfunction "2_2") (pintype "passive"))
    )
    (net (code "32") (name "Net-(P21-Pad2)") (class "Default")
      (node (ref "P21") (pin "2") (pinfunction "2_2") (pintype "passive"))
      (node (ref "R86") (pin "2") (pinfunction "2_2") (pintype "passive"))
    )
    (net (code "33") (name "Net-(U16-ADCOUT)") (class "Default")
      (node (ref "C90") (pin "2") (pinfunction "2_2") (pintype "passive"))
      (node (ref "U16") (pin "4") (pinfunction "ADCOUT_4") (pintype "output"))
      (node (ref "U19") (pin "5") (pinfunction "AIN_5") (pintype "input"))
    )
    (net (code "34") (name "Net-(U16-FILT)") (class "Default")
      (node (ref "C97") (pin "2") (pinfunction "2_2") (pintype "passive"))
      (node (ref "U16") (pin "5") (pinfunction "FILT_5") (pintype "bidirectional"))
    )
    (net (code "35") (name "Net-(U16-IN+)") (class "Default")
      (node (ref "P15") (pin "2") (pinfunction "2_2") (pintype "passive"))
      (node (ref "U16") (pin "8") (pinfunction "IN+_8") (pintype "input"))
    )
    (net (code "36") (name "Net-(U16-IN-)") (class "Default")
      (node (ref "P15") (pin "3") (pinfunction "3_3") (pintype "passive"))
      (node (ref "U16") (pin "1") (pinfunction "IN-_1") (pintype "input"))
    )
    (net (code "37") (name "Net-(U16-REF)") (class "Default")
      (node (ref "C86") (pin "1") (pinfunction "1_1") (pintype "passive"))
      (node (ref "R54") (pin "1") (pinfunction "1_1") (pintype "passive"))
      (node (ref "R55") (pin "2") (pinfunction "2_2") (pintype "passive"))
      (node (ref "U16") (pin "3") (pinfunction "REF_3") (pintype "input"))
    )
    (net (code "38") (name "Net-(U17-ADCOUT)") (class "Default")
      (node (ref "C103") (pin "2") (pinfunction "2_2") (pintype "passive"))
      (node (ref "U17") (pin "4") (pinfunction "ADCOUT_4") (pintype "output"))
      (node (ref "U18") (pin "5") (pinfunction "AIN_5") (pintype "input"))
    )
    (net (code "39") (name "Net-(U17-FILT)") (class "Default")
      (node (ref "C110") (pin "2") (pinfunction "2_2") (pintype "passive"))
      (node (ref "U17") (pin "5") (pinfunction "FILT_5") (pintype "bidirectional"))
    )
    (net (code "40") (name "Net-(U17-IN+)") (class "Default")
      (node (ref "P17") (pin "2") (pinfunction "2_2") (pintype "passive"))
      (node (ref "U17") (pin "8") (pinfunction "IN+_8") (pintype "input"))
    )
    (net (code "41") (name "Net-(U17-IN-)") (class "Default")
      (node (ref "P17") (pin "3") (pinfunction "3_3") (pintype "passive"))
      (node (ref "U17") (pin "1") (pinfunction "IN-_1") (pintype "input"))
    )
    (net (code "42") (name "Net-(U17-REF)") (class "Default")
      (node (ref "C99") (pin "1") (pinfunction "1_1") (pintype "passive"))
      (node (ref "R62") (pin "1") (pinfunction "1_1") (pintype "passive"))
      (node (ref "R63") (pin "2") (pinfunction "2_2") (pintype "passive"))
      (node (ref "U17") (pin "3") (pinfunction "REF_3") (pintype "input"))
    )
    (net (code "43") (name "TRIGGER_US") (class "Default")
      (node (ref "P19") (pin "2") (pinfunction "2_2") (pintype "passive"))
    )
  )
)
